# TPriiorityEncoder.net
KiCad netlist of a schematic drawn in Altium Designer
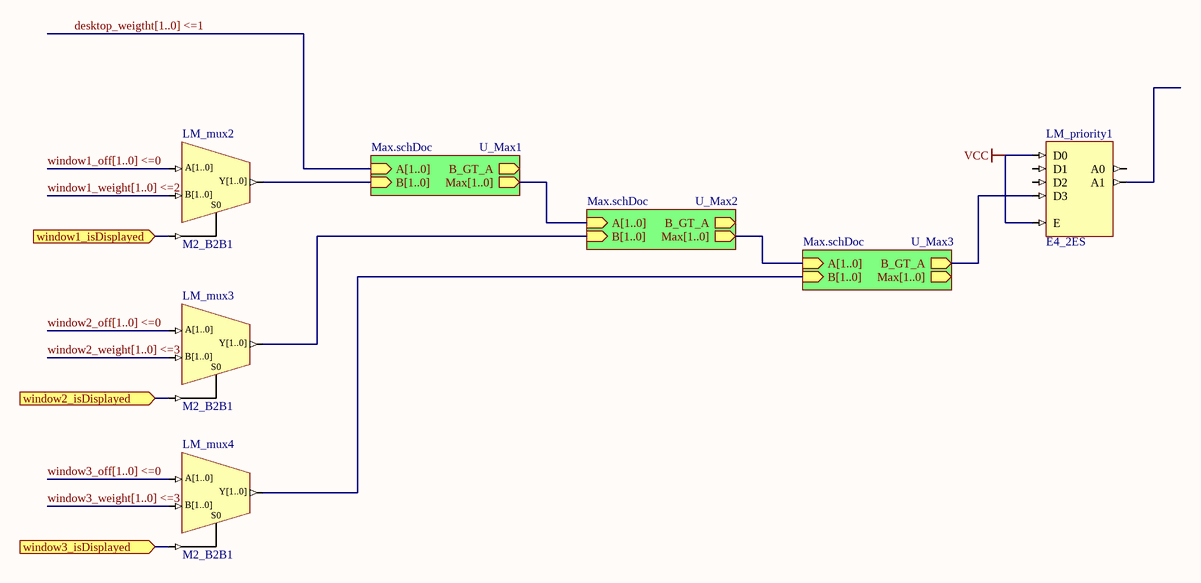
[diagram p0: TPriiorityEncoder.SchDoc]

(export (version "E")
  (design (tool "Eeschema 10.0.6"))
  (components
    (comp (ref "LM_mux2")
      (value "M2_B2B1")
      (description "2x2-Bit Bus to 1x2-Bit Bus Multiplexer")
      (fields (field (name "PUBLISHER") "Altium Limited"))
      (libsource (lib "FPGA Generic") (part "M2_B2B1"))
    )
    (comp (ref "LM_mux3")
      (value "M2_B2B1")
      (description "2x2-Bit Bus to 1x2-Bit Bus Multiplexer")
      (fields (field (name "PUBLISHER") "Altium Limited"))
      (libsource (lib "FPGA Generic") (part "M2_B2B1"))
    )
    (comp (ref "LM_mux4")
      (value "M2_B2B1")
      (description "2x2-Bit Bus to 1x2-Bit Bus Multiplexer")
      (fields (field (name "PUBLISHER") "Altium Limited"))
      (libsource (lib "FPGA Generic") (part "M2_B2B1"))
    )
    (comp (ref "LM_priority1")
      (value "E4_2ES")
      (description "4- to 2-Bit Priority Encoder with Enable, Single Pin Version")
      (fields (field (name "PUBLISHER") "Altium Limited"))
      (libsource (lib "FPGA Generic") (part "E4_2ES"))
    )
  )
  (nets
    (net (code "1") (name "/B[1..0]_1") (class "Default")
      (node (ref "LM_mux2") (pin "Y[1..0]") (pinfunction "Y[1..0]_Y[1..0]") (pintype "output"))
    )
    (net (code "2") (name "/B[1..0]_2") (class "Default")
      (node (ref "LM_mux4") (pin "Y[1..0]") (pinfunction "Y[1..0]_Y[1..0]") (pintype "output"))
    )
    (net (code "3") (name "/B[1..0]_3") (class "Default")
      (node (ref "LM_mux3") (pin "Y[1..0]") (pinfunction "Y[1..0]_Y[1..0]") (pintype "output"))
    )
    (net (code "4") (name "/B_GT_A") (class "Default")
      (node (ref "LM_priority1") (pin "D3") (pinfunction "D3_D3") (pintype "input"))
    )
    (net (code "11") (name "/window1_isDisplayed") (class "Default")
      (node (ref "LM_mux2") (pin "S0") (pinfunction "S0_S0") (pintype "input"))
    )
    (net (code "12") (name "/window1_off[1..0] <=0") (class "Default")
      (node (ref "LM_mux2") (pin "A[1..0]") (pinfunction "A[1..0]_A[1..0]") (pintype "input"))
    )
    (net (code "13") (name "/window1_weight[1..0] <=2") (class "Default")
      (node (ref "LM_mux2") (pin "B[1..0]") (pinfunction "B[1..0]_B[1..0]") (pintype "input"))
    )
    (net (code "14") (name "/window2_isDisplayed") (class "Default")
      (node (ref "LM_mux3") (pin "S0") (pinfunction "S0_S0") (pintype "input"))
    )
    (net (code "15") (name "/window2_off[1..0] <=0") (class "Default")
      (node (ref "LM_mux3") (pin "A[1..0]") (pinfunction "A[1..0]_A[1..0]") (pintype "input"))
    )
    (net (code "16") (name "/window2_weight[1..0] <=3") (class "Default")
      (node (ref "LM_mux3") (pin "B[1..0]") (pinfunction "B[1..0]_B[1..0]") (pintype "input"))
    )
    (net (code "17") (name "/window3_isDisplayed") (class "Default")
      (node (ref "LM_mux4") (pin "S0") (pinfunction "S0_S0") (pintype "input"))
    )
    (net (code "18") (name "/window3_off[1..0] <=0") (class "Default")
      (node (ref "LM_mux4") (pin "A[1..0]") (pinfunction "A[1..0]_A[1..0]") (pintype "input"))
    )
    (net (code "19") (name "/window3_weight[1..0] <=3") (class "Default")
      (node (ref "LM_mux4") (pin "B[1..0]") (pinfunction "B[1..0]_B[1..0]") (pintype "input"))
    )
    (net (code "20") (name "VCC") (class "Default")
      (node (ref "LM_priority1") (pin "D0") (pinfunction "D0_D0") (pintype "input"))
      (node (ref "LM_priority1") (pin "E") (pinfunction "E_E") (pintype "input"))
    )
    (net (code "21") (name "unconnected-(LM_priority1-PadA0)") (class "Default")
      (node (ref "LM_priority1") (pin "A0") (pinfunction "A0_A0") (pintype "output"))
    )
    (net (code "22") (name "unconnected-(LM_priority1-PadA1)") (class "Default")
      (node (ref "LM_priority1") (pin "A1") (pinfunction "A1_A1") (pintype "output"))
    )
    (net (code "23") (name "unconnected-(LM_priority1-PadD1)") (class "Default")
      (node (ref "LM_priority1") (pin "D1") (pinfunction "D1_D1") (pintype "input"))
    )
    (net (code "24") (name "unconnected-(LM_priority1-PadD2)") (class "Default")
      (node (ref "LM_priority1") (pin "D2") (pinfunction "D2_D2") (pintype "input"))
    )
  )
)
